# DDRMemory.net
KiCad netlist of a schematic drawn in Altium Designer
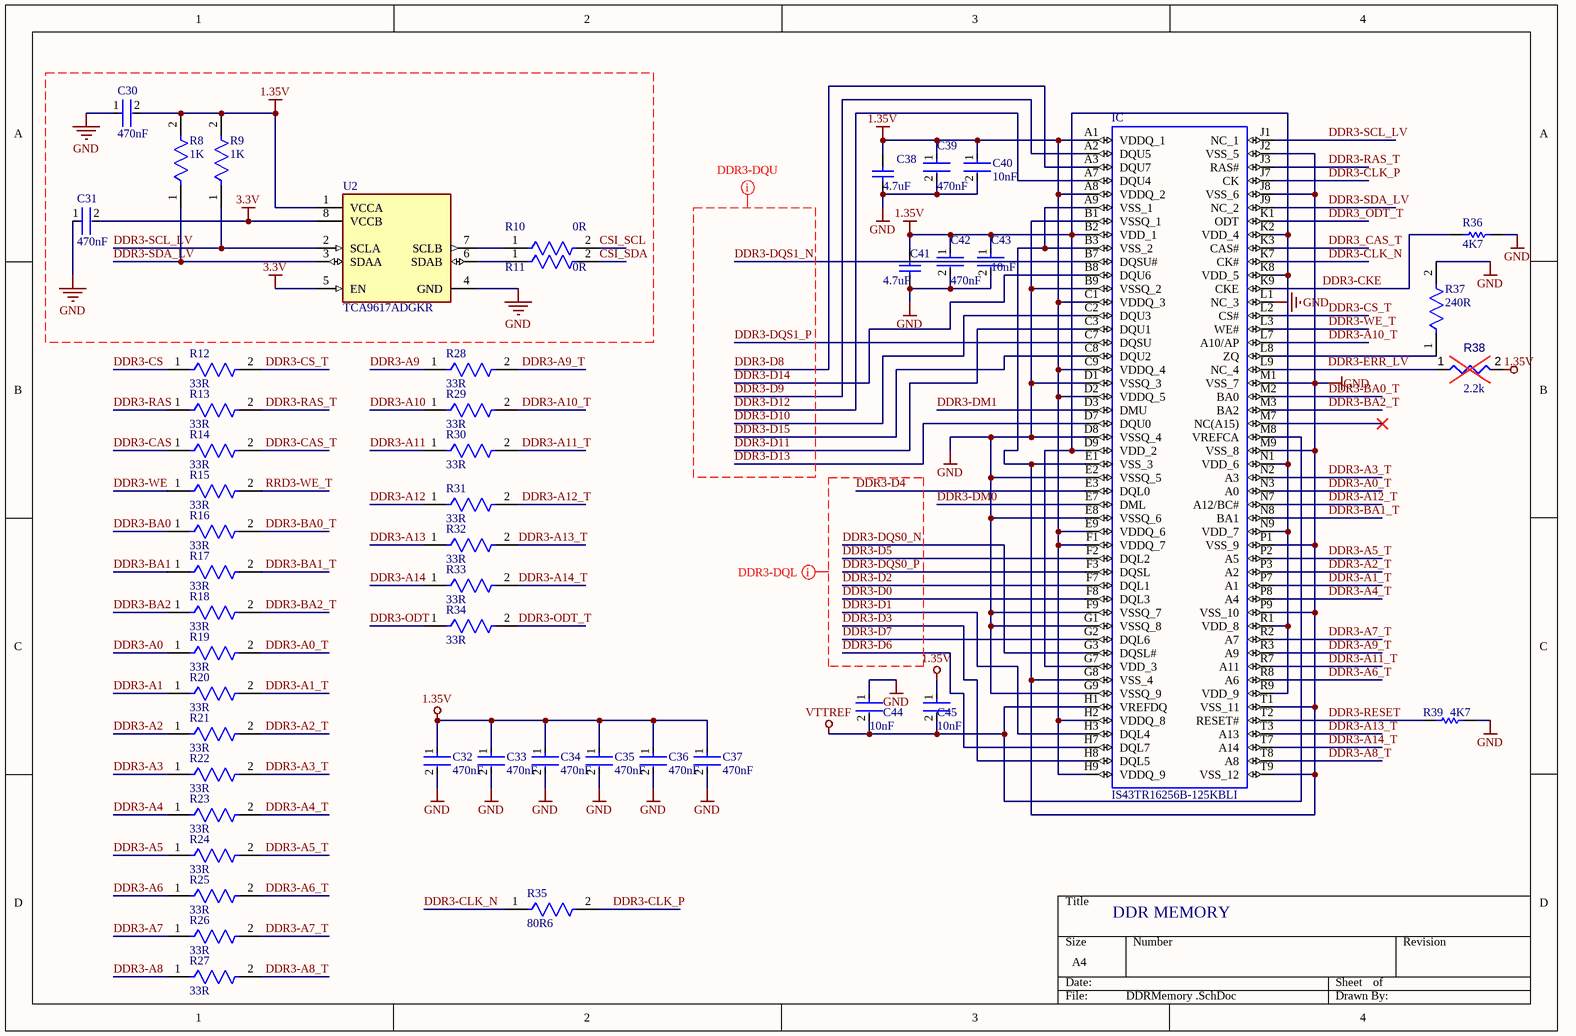
[diagram p0: DDRMemory .SchDoc]

(export (version "E")
  (design (tool "Eeschema 10.0.6"))
  (components
    (comp (ref "C30")
      (value "470nF")
      (footprint "FP-CC0603-DA-MFG")
      (description "CAP CER 0.47UF 6.3V X5R 0603")
      (fields
        (field (name "VOLTAGE") "6.3 V")
        (field (name "OCTOPART") "https://octopart.com/cc0603krx5r5bb474-yageo-9288194")
      )
      (libsource (lib "Altium Content Vault") (part "11868f565c42a9108669ba33697ecf6"))
    )
    (comp (ref "C31")
      (value "470nF")
      (footprint "FP-CC0603-DA-MFG")
      (description "CAP CER 0.47UF 6.3V X5R 0603")
      (fields
        (field (name "VOLTAGE") "6.3 V")
        (field (name "OCTOPART") "https://octopart.com/cc0603krx5r5bb474-yageo-9288194")
      )
      (libsource (lib "Altium Content Vault") (part "11868f565c42a9108669ba33697ecf6"))
    )
    (comp (ref "C32")
      (value "470nF")
      (footprint "FP-0603-L_1_6_0_1-W_0_8_0-IPC_C")
      (description "None")
      (fields (field (name "TOLERANCE") "20%"))
      (libsource (lib "Altium Content Vault") (part "02cd4be3c70576c341d710602a673aa"))
    )
    (comp (ref "C33")
      (value "470nF")
      (footprint "FP-0603-L_1_6_0_1-W_0_8_0-IPC_C")
      (description "None")
      (fields (field (name "TOLERANCE") "20%"))
      (libsource (lib "Altium Content Vault") (part "02cd4be3c70576c341d710602a673aa"))
    )
    (comp (ref "C34")
      (value "470nF")
      (footprint "FP-0603-L_1_6_0_1-W_0_8_0-IPC_C")
      (description "None")
      (fields (field (name "TOLERANCE") "20%"))
      (libsource (lib "Altium Content Vault") (part "02cd4be3c70576c341d710602a673aa"))
    )
    (comp (ref "C35")
      (value "470nF")
      (footprint "FP-0603-L_1_6_0_1-W_0_8_0-IPC_C")
      (description "None")
      (fields (field (name "TOLERANCE") "20%"))
      (libsource (lib "Altium Content Vault") (part "02cd4be3c70576c341d710602a673aa"))
    )
    (comp (ref "C36")
      (value "470nF")
      (footprint "FP-0603-L_1_6_0_1-W_0_8_0-IPC_C")
      (description "None")
      (fields (field (name "TOLERANCE") "20%"))
      (libsource (lib "Altium Content Vault") (part "02cd4be3c70576c341d710602a673aa"))
    )
    (comp (ref "C37")
      (value "470nF")
      (footprint "FP-0603-L_1_6_0_1-W_0_8_0-IPC_C")
      (description "None")
      (fields (field (name "TOLERANCE") "20%"))
      (libsource (lib "Altium Content Vault") (part "02cd4be3c70576c341d710602a673aa"))
    )
    (comp (ref "C38")
      (value "4.7uF")
      (footprint "CAPC1005X71X25NL10T15")
      (fields
        (field (name "PART NUMBER") "0402ZD475MAT2A")
        (field (name "MANUFACTURER") "AVX Interconnect / Elco")
      )
      (libsource (lib "Altium Content Vault") (part "CAP"))
    )
    (comp (ref "C39")
      (value "470nF")
      (footprint "FP-0402-L_1_0_1-W_0_5_0_1-IPC_C")
      (description "General Purpose Ceramic Capacitor, 0402, 470nF, 10%, X7R, 15%, 10V")
      (libsource (lib "Altium Content Vault") (part "b4654b650e69147ec39a6b967a45e02"))
    )
    (comp (ref "C40")
      (value "10nF")
      (footprint "FP-CC0402-MFG")
      (description "CAP CER 10000PF 10V X7R 0402")
      (fields
        (field (name "MANUFACTURER PART NUMBER") "CC0402MRX7R6BB103")
        (field (name "MANUFACTURER") "YAGEO")
      )
      (libsource (lib "Altium Content Vault") (part "11868f565c42a9108669ba33697ecf6"))
    )
    (comp (ref "C41")
      (value "4.7uF")
      (footprint "CAPC1005X71X25NL10T15")
      (fields
        (field (name "PART NUMBER") "0402ZD475MAT2A")
        (field (name "MANUFACTURER") "AVX Interconnect / Elco")
      )
      (libsource (lib "Altium Content Vault") (part "CAP"))
    )
    (comp (ref "C42")
      (value "470nF")
      (footprint "FP-0402-L_1_0_1-W_0_5_0_1-IPC_C")
      (description "General Purpose Ceramic Capacitor, 0402, 470nF, 10%, X7R, 15%, 10V")
      (libsource (lib "Altium Content Vault") (part "b4654b650e69147ec39a6b967a45e02"))
    )
    (comp (ref "C43")
      (value "10nF")
      (footprint "FP-CC0402-MFG")
      (description "CAP CER 10000PF 10V X7R 0402")
      (fields
        (field (name "MANUFACTURER PART NUMBER") "CC0402MRX7R6BB103")
        (field (name "MANUFACTURER") "YAGEO")
      )
      (libsource (lib "Altium Content Vault") (part "11868f565c42a9108669ba33697ecf6"))
    )
    (comp (ref "C44")
      (value "10nF")
      (footprint "FP-CC0402-MFG")
      (description "CAP CER 10000PF 10V X7R 0402")
      (fields
        (field (name "MANUFACTURER PART NUMBER") "CC0402MRX7R6BB103")
        (field (name "MANUFACTURER") "YAGEO")
      )
      (libsource (lib "Altium Content Vault") (part "11868f565c42a9108669ba33697ecf6"))
    )
    (comp (ref "C45")
      (value "10nF")
      (footprint "FP-CC0402-MFG")
      (description "CAP CER 10000PF 10V X7R 0402")
      (fields
        (field (name "MANUFACTURER PART NUMBER") "CC0402MRX7R6BB103")
        (field (name "MANUFACTURER") "YAGEO")
      )
      (libsource (lib "Altium Content Vault") (part "11868f565c42a9108669ba33697ecf6"))
    )
    (comp (ref "IC")
      (value "IS43TR16256B-125KBLI")
      (footprint "BGA96C80P9X16_900X1300X120:BGA96C80P9X16_900X1300X120")
      (description "SDRAM - DDR3 Memory IC 4Gb (256M x 16) Parallel 800MHz 20ns 96-TWBGA (9x13)")
      (fields (field (name "MF") "ISSI, Integrated Silicon Solution Inc"))
      (libsource (lib "IS43TR16256B-125KBLI") (part "IS43TR16256B-125KBLI"))
    )
    (comp (ref "R8")
      (value "1K")
      (footprint "FP-AC0603-IPC_B")
      (description "RES 1kΩ 1.00% 0.2W 0603")
      (libsource (lib "Altium Content Vault") (part "1029c3af85768c4190bb7ad29bc67b5"))
    )
    (comp (ref "R9")
      (value "1K")
      (footprint "FP-AC0603-IPC_B")
      (description "RES 1kΩ 1.00% 0.2W 0603")
      (libsource (lib "Altium Content Vault") (part "1029c3af85768c4190bb7ad29bc67b5"))
    )
    (comp (ref "R10")
      (value "0R")
      (footprint "FP-AC0603-IPC_A")
      (description "RES 0Ω 0.00% 0.1W 0603")
      (fields (field (name "TOLERANCE") "5%"))
      (libsource (lib "Altium Content Vault") (part "1029c3af85768c4190bb7ad29bc67b5"))
    )
    (comp (ref "R11")
      (value "0R")
      (footprint "FP-AC0603-IPC_A")
      (description "RES 0Ω 0.00% 0.1W 0603")
      (fields (field (name "TOLERANCE") "5%"))
      (libsource (lib "Altium Content Vault") (part "1029c3af85768c4190bb7ad29bc67b5"))
    )
    (comp (ref "R12")
      (value "33R")
      (footprint "FP-AF0201-IPC_A")
      (description "Anti-Sulfurated Chip Resistors Automotive Grade 33Ω 5% 200ppm/°C 0201")
      (fields (field (name "TOLERANCE") "5%"))
      (libsource (lib "Altium Content Vault") (part "1029c3af85768c4190bb7ad29bc67b5"))
    )
    (comp (ref "R13")
      (value "33R")
      (footprint "FP-AF0201-IPC_A")
      (description "Anti-Sulfurated Chip Resistors Automotive Grade 33Ω 5% 200ppm/°C 0201")
      (fields (field (name "TOLERANCE") "5%"))
      (libsource (lib "Altium Content Vault") (part "1029c3af85768c4190bb7ad29bc67b5"))
    )
    (comp (ref "R14")
      (value "33R")
      (footprint "FP-AF0201-IPC_A")
      (description "Anti-Sulfurated Chip Resistors Automotive Grade 33Ω 5% 200ppm/°C 0201")
      (fields (field (name "TOLERANCE") "5%"))
      (libsource (lib "Altium Content Vault") (part "1029c3af85768c4190bb7ad29bc67b5"))
    )
    (comp (ref "R15")
      (value "33R")
      (footprint "FP-AF0201-IPC_A")
      (description "Anti-Sulfurated Chip Resistors Automotive Grade 33Ω 5% 200ppm/°C 0201")
      (fields (field (name "TOLERANCE") "5%"))
      (libsource (lib "Altium Content Vault") (part "1029c3af85768c4190bb7ad29bc67b5"))
    )
    (comp (ref "R16")
      (value "33R")
      (footprint "FP-AF0201-IPC_A")
      (description "Anti-Sulfurated Chip Resistors Automotive Grade 33Ω 5% 200ppm/°C 0201")
      (fields (field (name "TOLERANCE") "5%"))
      (libsource (lib "Altium Content Vault") (part "1029c3af85768c4190bb7ad29bc67b5"))
    )
    (comp (ref "R17")
      (value "33R")
      (footprint "FP-AF0201-IPC_A")
      (description "Anti-Sulfurated Chip Resistors Automotive Grade 33Ω 5% 200ppm/°C 0201")
      (fields (field (name "TOLERANCE") "5%"))
      (libsource (lib "Altium Content Vault") (part "1029c3af85768c4190bb7ad29bc67b5"))
    )
    (comp (ref "R18")
      (value "33R")
      (footprint "FP-AF0201-IPC_A")
      (description "Anti-Sulfurated Chip Resistors Automotive Grade 33Ω 5% 200ppm/°C 0201")
      (fields (field (name "TOLERANCE") "5%"))
      (libsource (lib "Altium Content Vault") (part "1029c3af85768c4190bb7ad29bc67b5"))
    )
    (comp (ref "R19")
      (value "33R")
      (footprint "FP-AF0201-IPC_A")
      (description "Anti-Sulfurated Chip Resistors Automotive Grade 33Ω 5% 200ppm/°C 0201")
      (fields (field (name "TOLERANCE") "5%"))
      (libsource (lib "Altium Content Vault") (part "1029c3af85768c4190bb7ad29bc67b5"))
    )
    (comp (ref "R20")
      (value "33R")
      (footprint "FP-AF0201-IPC_A")
      (description "Anti-Sulfurated Chip Resistors Automotive Grade 33Ω 5% 200ppm/°C 0201")
      (fields (field (name "TOLERANCE") "5%"))
      (libsource (lib "Altium Content Vault") (part "1029c3af85768c4190bb7ad29bc67b5"))
    )
    (comp (ref "R21")
      (value "33R")
      (footprint "FP-AF0201-IPC_A")
      (description "Anti-Sulfurated Chip Resistors Automotive Grade 33Ω 5% 200ppm/°C 0201")
      (fields (field (name "TOLERANCE") "5%"))
      (libsource (lib "Altium Content Vault") (part "1029c3af85768c4190bb7ad29bc67b5"))
    )
    (comp (ref "R22")
      (value "33R")
      (footprint "FP-AF0201-IPC_A")
      (description "Anti-Sulfurated Chip Resistors Automotive Grade 33Ω 5% 200ppm/°C 0201")
      (fields (field (name "TOLERANCE") "5%"))
      (libsource (lib "Altium Content Vault") (part "1029c3af85768c4190bb7ad29bc67b5"))
    )
    (comp (ref "R23")
      (value "33R")
      (footprint "FP-AF0201-IPC_A")
      (description "Anti-Sulfurated Chip Resistors Automotive Grade 33Ω 5% 200ppm/°C 0201")
      (fields (field (name "TOLERANCE") "5%"))
      (libsource (lib "Altium Content Vault") (part "1029c3af85768c4190bb7ad29bc67b5"))
    )
    (comp (ref "R24")
      (value "33R")
      (footprint "FP-AF0201-IPC_A")
      (description "Anti-Sulfurated Chip Resistors Automotive Grade 33Ω 5% 200ppm/°C 0201")
      (fields (field (name "TOLERANCE") "5%"))
      (libsource (lib "Altium Content Vault") (part "1029c3af85768c4190bb7ad29bc67b5"))
    )
    (comp (ref "R25")
      (value "33R")
      (footprint "FP-AF0201-IPC_A")
      (description "Anti-Sulfurated Chip Resistors Automotive Grade 33Ω 5% 200ppm/°C 0201")
      (fields (field (name "TOLERANCE") "5%"))
      (libsource (lib "Altium Content Vault") (part "1029c3af85768c4190bb7ad29bc67b5"))
    )
    (comp (ref "R26")
      (value "33R")
      (footprint "FP-AF0201-IPC_A")
      (description "Anti-Sulfurated Chip Resistors Automotive Grade 33Ω 5% 200ppm/°C 0201")
      (fields (field (name "TOLERANCE") "5%"))
      (libsource (lib "Altium Content Vault") (part "1029c3af85768c4190bb7ad29bc67b5"))
    )
    (comp (ref "R27")
      (value "33R")
      (footprint "FP-AF0201-IPC_A")
      (description "Anti-Sulfurated Chip Resistors Automotive Grade 33Ω 5% 200ppm/°C 0201")
      (fields (field (name "TOLERANCE") "5%"))
      (libsource (lib "Altium Content Vault") (part "1029c3af85768c4190bb7ad29bc67b5"))
    )
    (comp (ref "R28")
      (value "33R")
      (footprint "FP-AF0201-IPC_A")
      (description "Anti-Sulfurated Chip Resistors Automotive Grade 33Ω 5% 200ppm/°C 0201")
      (fields (field (name "TOLERANCE") "5%"))
      (libsource (lib "Altium Content Vault") (part "1029c3af85768c4190bb7ad29bc67b5"))
    )
    (comp (ref "R29")
      (value "33R")
      (footprint "FP-AF0201-IPC_A")
      (description "Anti-Sulfurated Chip Resistors Automotive Grade 33Ω 5% 200ppm/°C 0201")
      (fields (field (name "TOLERANCE") "5%"))
      (libsource (lib "Altium Content Vault") (part "1029c3af85768c4190bb7ad29bc67b5"))
    )
    (comp (ref "R30")
      (value "33R")
      (footprint "FP-AF0201-IPC_A")
      (description "Anti-Sulfurated Chip Resistors Automotive Grade 33Ω 5% 200ppm/°C 0201")
      (fields (field (name "TOLERANCE") "5%"))
      (libsource (lib "Altium Content Vault") (part "1029c3af85768c4190bb7ad29bc67b5"))
    )
    (comp (ref "R31")
      (value "33R")
      (footprint "FP-AF0201-IPC_A")
      (description "Anti-Sulfurated Chip Resistors Automotive Grade 33Ω 5% 200ppm/°C 0201")
      (fields (field (name "TOLERANCE") "5%"))
      (libsource (lib "Altium Content Vault") (part "1029c3af85768c4190bb7ad29bc67b5"))
    )
    (comp (ref "R32")
      (value "33R")
      (footprint "FP-AF0201-IPC_A")
      (description "Anti-Sulfurated Chip Resistors Automotive Grade 33Ω 5% 200ppm/°C 0201")
      (fields (field (name "TOLERANCE") "5%"))
      (libsource (lib "Altium Content Vault") (part "1029c3af85768c4190bb7ad29bc67b5"))
    )
    (comp (ref "R33")
      (value "33R")
      (footprint "FP-AF0201-IPC_A")
      (description "Anti-Sulfurated Chip Resistors Automotive Grade 33Ω 5% 200ppm/°C 0201")
      (fields (field (name "TOLERANCE") "5%"))
      (libsource (lib "Altium Content Vault") (part "1029c3af85768c4190bb7ad29bc67b5"))
    )
    (comp (ref "R34")
      (value "33R")
      (footprint "FP-AF0201-IPC_A")
      (description "Anti-Sulfurated Chip Resistors Automotive Grade 33Ω 5% 200ppm/°C 0201")
      (fields (field (name "TOLERANCE") "5%"))
      (libsource (lib "Altium Content Vault") (part "1029c3af85768c4190bb7ad29bc67b5"))
    )
    (comp (ref "R35")
      (value "80R6")
      (footprint "FP-RQ732B-IPC_C")
      (description "RQ732B 1206 80.6Ω 0.4W 10ppm/°C 0.1% 200V")
      (fields (field (name "TOLERANCE") "0.1%") (field (name "MANUFACTURER PART NUMBER") "RQ73C2B80R6BTDF"))
      (libsource (lib "Altium Content Vault") (part "1029c3af85768c4190bb7ad29bc67b5"))
    )
    (comp (ref "R36")
      (value "4K7")
      (footprint "RESC1812(4532)_N")
      (description "4K7 0.75W 5% 1812 (4532 Metric)  SMD")
      (fields (field (name "TOLERANCE") "5 %") (field (name "POWER") "0.75 W"))
      (libsource (lib "Altium Content Vault") (part "RES"))
    )
    (comp (ref "R37")
      (value "240R")
      (footprint "FP-RNCP0402-IPC_C")
      (description "240Ω ±1% 0.1W 0402 High Power Anti-Sulfur Thin Film Chip Resistor")
      (fields (field (name "TOLERANCE") "1%"))
      (libsource (lib "Altium Content Vault") (part "1029c3af85768c4190bb7ad29bc67b5"))
    )
    (comp (ref "R38")
      (value "2.2k")
      (footprint "RESC0402(1005)_L")
      (description "2K2 0.063W 5% 0402 (1005 Metric)  SMD")
      (fields (field (name "TOLERANCE") "5%") (field (name "POWER") "63mW"))
      (libsource (lib "Meenakshi Shyam") (part "2D2KR2J"))
    )
    (comp (ref "R39")
      (value "4K7")
      (footprint "RESC1812(4532)_N")
      (description "4K7 0.75W 5% 1812 (4532 Metric)  SMD")
      (fields (field (name "TOLERANCE") "5 %") (field (name "POWER") "0.75 W"))
      (libsource (lib "Altium Content Vault") (part "RES"))
    )
    (comp (ref "U2")
      (value "TCA9617ADGKR")
      (footprint "FP-DGK0008A-MFG")
      (description "IC TRNSLTR BIDIRECTIONAL 8VSSOP")
      (fields
        (field (name "MANUFACTURER") "Texas Instruments")
        (field (name "OCTOPART") "https://octopart.com/tca9617adgkr-texas+instruments-29775809")
      )
      (libsource (lib "Altium Content Vault") (part "d64de71481be55f428f1ea82f36f333"))
    )
  )
  (nets
    (net (code "1") (name "/CSI_SCL") (class "Default")
      (node (ref "R10") (pin "2") (pinfunction "2_2") (pintype "passive"))
    )
    (net (code "2") (name "/CSI_SDA") (class "Default")
      (node (ref "R11") (pin "2") (pinfunction "2_2") (pintype "passive"))
    )
    (net (code "3") (name "/DDR3-A0") (class "Default")
      (node (ref "R19") (pin "1") (pinfunction "1_1") (pintype "passive"))
    )
    (net (code "4") (name "/DDR3-A0_T") (class "Default")
      (node (ref "IC") (pin "N3") (pinfunction "A0_N3") (pintype "bidirectional"))
      (node (ref "R19") (pin "2") (pinfunction "2_2") (pintype "passive"))
    )
    (net (code "5") (name "/DDR3-A1") (class "Default")
      (node (ref "R20") (pin "1") (pinfunction "1_1") (pintype "passive"))
    )
    (net (code "6") (name "/DDR3-A1_T") (class "Default")
      (node (ref "IC") (pin "P7") (pinfunction "A1_P7") (pintype "bidirectional"))
      (node (ref "R20") (pin "2") (pinfunction "2_2") (pintype "passive"))
    )
    (net (code "7") (name "/DDR3-A2") (class "Default")
      (node (ref "R21") (pin "1") (pinfunction "1_1") (pintype "passive"))
    )
    (net (code "8") (name "/DDR3-A2_T") (class "Default")
      (node (ref "IC") (pin "P3") (pinfunction "A2_P3") (pintype "bidirectional"))
      (node (ref "R21") (pin "2") (pinfunction "2_2") (pintype "passive"))
    )
    (net (code "9") (name "/DDR3-A3") (class "Default")
      (node (ref "R22") (pin "1") (pinfunction "1_1") (pintype "passive"))
    )
    (net (code "10") (name "/DDR3-A3_T") (class "Default")
      (node (ref "IC") (pin "N2") (pinfunction "A3_N2") (pintype "bidirectional"))
      (node (ref "R22") (pin "2") (pinfunction "2_2") (pintype "passive"))
    )
    (net (code "11") (name "/DDR3-A4") (class "Default")
      (node (ref "R23") (pin "1") (pinfunction "1_1") (pintype "passive"))
    )
    (net (code "12") (name "/DDR3-A4_T") (class "Default")
      (node (ref "IC") (pin "P8") (pinfunction "A4_P8") (pintype "bidirectional"))
      (node (ref "R23") (pin "2") (pinfunction "2_2") (pintype "passive"))
    )
    (net (code "13") (name "/DDR3-A5") (class "Default")
      (node (ref "R24") (pin "1") (pinfunction "1_1") (pintype "passive"))
    )
    (net (code "14") (name "/DDR3-A5_T") (class "Default")
      (node (ref "IC") (pin "P2") (pinfunction "A5_P2") (pintype "bidirectional"))
      (node (ref "R24") (pin "2") (pinfunction "2_2") (pintype "passive"))
    )
    (net (code "15") (name "/DDR3-A6") (class "Default")
      (node (ref "R25") (pin "1") (pinfunction "1_1") (pintype "passive"))
    )
    (net (code "16") (name "/DDR3-A6_T") (class "Default")
      (node (ref "IC") (pin "R8") (pinfunction "A6_R8") (pintype "bidirectional"))
      (node (ref "R25") (pin "2") (pinfunction "2_2") (pintype "passive"))
    )
    (net (code "17") (name "/DDR3-A7") (class "Default")
      (node (ref "R26") (pin "1") (pinfunction "1_1") (pintype "passive"))
    )
    (net (code "18") (name "/DDR3-A7_T") (class "Default")
      (node (ref "IC") (pin "R2") (pinfunction "A7_R2") (pintype "bidirectional"))
      (node (ref "R26") (pin "2") (pinfunction "2_2") (pintype "passive"))
    )
    (net (code "19") (name "/DDR3-A8") (class "Default")
      (node (ref "R27") (pin "1") (pinfunction "1_1") (pintype "passive"))
    )
    (net (code "20") (name "/DDR3-A8_T") (class "Default")
      (node (ref "IC") (pin "T8") (pinfunction "A8_T8") (pintype "bidirectional"))
      (node (ref "R27") (pin "2") (pinfunction "2_2") (pintype "passive"))
    )
    (net (code "21") (name "/DDR3-A9") (class "Default")
      (node (ref "R28") (pin "1") (pinfunction "1_1") (pintype "passive"))
    )
    (net (code "22") (name "/DDR3-A9_T") (class "Default")
      (node (ref "IC") (pin "R3") (pinfunction "A9_R3") (pintype "bidirectional"))
      (node (ref "R28") (pin "2") (pinfunction "2_2") (pintype "passive"))
    )
    (net (code "23") (name "/DDR3-A10") (class "Default")
      (node (ref "R29") (pin "1") (pinfunction "1_1") (pintype "passive"))
    )
    (net (code "24") (name "/DDR3-A10_T") (class "Default")
      (node (ref "IC") (pin "L7") (pinfunction "A10/AP_L7") (pintype "bidirectional"))
      (node (ref "R29") (pin "2") (pinfunction "2_2") (pintype "passive"))
    )
    (net (code "25") (name "/DDR3-A11") (class "Default")
      (node (ref "R30") (pin "1") (pinfunction "1_1") (pintype "passive"))
    )
    (net (code "26") (name "/DDR3-A11_T") (class "Default")
      (node (ref "IC") (pin "R7") (pinfunction "A11_R7") (pintype "bidirectional"))
      (node (ref "R30") (pin "2") (pinfunction "2_2") (pintype "passive"))
    )
    (net (code "27") (name "/DDR3-A12") (class "Default")
      (node (ref "R31") (pin "1") (pinfunction "1_1") (pintype "passive"))
    )
    (net (code "28") (name "/DDR3-A12_T") (class "Default")
      (node (ref "IC") (pin "N7") (pinfunction "A12/BC#_N7") (pintype "bidirectional"))
      (node (ref "R31") (pin "2") (pinfunction "2_2") (pintype "passive"))
    )
    (net (code "29") (name "/DDR3-A13") (class "Default")
      (node (ref "R32") (pin "1") (pinfunction "1_1") (pintype "passive"))
    )
    (net (code "30") (name "/DDR3-A13_T") (class "Default")
      (node (ref "IC") (pin "T3") (pinfunction "A13_T3") (pintype "bidirectional"))
      (node (ref "R32") (pin "2") (pinfunction "2_2") (pintype "passive"))
    )
    (net (code "31") (name "/DDR3-A14") (class "Default")
      (node (ref "R33") (pin "1") (pinfunction "1_1") (pintype "passive"))
    )
    (net (code "32") (name "/DDR3-A14_T") (class "Default")
      (node (ref "IC") (pin "T7") (pinfunction "A14_T7") (pintype "bidirectional"))
      (node (ref "R33") (pin "2") (pinfunction "2_2") (pintype "passive"))
    )
    (net (code "33") (name "/DDR3-BA0") (class "Default")
      (node (ref "R16") (pin "1") (pinfunction "1_1") (pintype "passive"))
    )
    (net (code "34") (name "/DDR3-BA0_T") (class "Default")
      (node (ref "IC") (pin "M2") (pinfunction "BA0_M2") (pintype "bidirectional"))
      (node (ref "R16") (pin "2") (pinfunction "2_2") (pintype "passive"))
    )
    (net (code "35") (name "/DDR3-BA1") (class "Default")
      (node (ref "R17") (pin "1") (pinfunction "1_1") (pintype "passive"))
    )
    (net (code "36") (name "/DDR3-BA1_T") (class "Default")
      (node (ref "IC") (pin "N8") (pinfunction "BA1_N8") (pintype "bidirectional"))
      (node (ref "R17") (pin "2") (pinfunction "2_2") (pintype "passive"))
    )
    (net (code "37") (name "/DDR3-BA2") (class "Default")
      (node (ref "R18") (pin "1") (pinfunction "1_1") (pintype "passive"))
    )
    (net (code "38") (name "/DDR3-BA2_T") (class "Default")
      (node (ref "IC") (pin "M3") (pinfunction "BA2_M3") (pintype "bidirectional"))
      (node (ref "R18") (pin "2") (pinfunction "2_2") (pintype "passive"))
    )
    (net (code "39") (name "/DDR3-CAS") (class "Default")
      (node (ref "R14") (pin "1") (pinfunction "1_1") (pintype "passive"))
    )
    (net (code "40") (name "/DDR3-CAS_T") (class "Default")
      (node (ref "R14") (pin "2") (pinfunction "2_2") (pintype "passive"))
    )
    (net (code "41") (name "/DDR3-CKE") (class "Default")
      (node (ref "IC") (pin "K9") (pinfunction "CKE_K9") (pintype "bidirectional"))
      (node (ref "R36") (pin "1") (pinfunction "1_1") (pintype "passive"))
    )
    (net (code "42") (name "/DDR3-CLK_N") (class "Default")
      (node (ref "IC") (pin "K7") (pinfunction "CK#_K7") (pintype "bidirectional"))
      (node (ref "R35") (pin "1") (pinfunction "1_1") (pintype "passive"))
    )
    (net (code "43") (name "/DDR3-CLK_P") (class "Default")
      (node (ref "IC") (pin "J7") (pinfunction "CK_J7") (pintype "bidirectional"))
      (node (ref "R35") (pin "2") (pinfunction "2_2") (pintype "passive"))
    )
    (net (code "44") (name "/DDR3-CS") (class "Default")
      (node (ref "R12") (pin "1") (pinfunction "1_1") (pintype "passive"))
    )
    (net (code "45") (name "/DDR3-CS_T") (class "Default")
      (node (ref "IC") (pin "L2") (pinfunction "CS#_L2") (pintype "bidirectional"))
      (node (ref "R12") (pin "2") (pinfunction "2_2") (pintype "passive"))
    )
    (net (code "46") (name "/DDR3-D0") (class "Default")
      (node (ref "IC") (pin "F8") (pinfunction "DQL3_F8") (pintype "bidirectional"))
    )
    (net (code "47") (name "/DDR3-D1") (class "Default")
      (node (ref "IC") (pin "H3") (pinfunction "DQL4_H3") (pintype "bidirectional"))
    )
    (net (code "48") (name "/DDR3-D2") (class "Default")
      (node (ref "IC") (pin "F7") (pinfunction "DQL1_F7") (pintype "bidirectional"))
    )
    (net (code "49") (name "/DDR3-D3") (class "Default")
      (node (ref "IC") (pin "H8") (pinfunction "DQL5_H8") (pintype "bidirectional"))
    )
    (net (code "50") (name "/DDR3-D4") (class "Default")
      (node (ref "IC") (pin "E3") (pinfunction "DQL0_E3") (pintype "bidirectional"))
    )
    (net (code "51") (name "/DDR3-D5") (class "Default")
      (node (ref "IC") (pin "F2") (pinfunction "DQL2_F2") (pintype "bidirectional"))
    )
    (net (code "52") (name "/DDR3-D6") (class "Default")
      (node (ref "IC") (pin "H7") (pinfunction "DQL7_H7") (pintype "bidirectional"))
    )
    (net (code "53") (name "/DDR3-D7") (class "Default")
      (node (ref "IC") (pin "G2") (pinfunction "DQL6_G2") (pintype "bidirectional"))
    )
    (net (code "54") (name "/DDR3-D8") (class "Default")
      (node (ref "IC") (pin "A3") (pinfunction "DQU7_A3") (pintype "bidirectional"))
    )
    (net (code "55") (name "/DDR3-D9") (class "Default")
      (node (ref "IC") (pin "A2") (pinfunction "DQU5_A2") (pintype "bidirectional"))
    )
    (net (code "56") (name "/DDR3-D10") (class "Default")
      (node (ref "IC") (pin "C2") (pinfunction "DQU3_C2") (pintype "bidirectional"))
    )
    (net (code "57") (name "/DDR3-D11") (class "Default")
      (node (ref "IC") (pin "C3") (pinfunction "DQU1_C3") (pintype "bidirectional"))
    )
    (net (code "58") (name "/DDR3-D12") (class "Default")
      (node (ref "IC") (pin "A7") (pinfunction "DQU4_A7") (pintype "bidirectional"))
    )
    (net (code "59") (name "/DDR3-D13") (class "Default")
      (node (ref "IC") (pin "D7") (pinfunction "DQU0_D7") (pintype "bidirectional"))
    )
    (net (code "60") (name "/DDR3-D14") (class "Default")
      (node (ref "IC") (pin "B8") (pinfunction "DQU6_B8") (pintype "bidirectional"))
    )
    (net (code "61") (name "/DDR3-D15") (class "Default")
      (node (ref "IC") (pin "C8") (pinfunction "DQU2_C8") (pintype "bidirectional"))
    )
    (net (code "62") (name "/DDR3-DM0") (class "Default")
      (node (ref "IC") (pin "E7") (pinfunction "DML_E7") (pintype "bidirectional"))
    )
    (net (code "63") (name "/DDR3-DM1") (class "Default")
      (node (ref "IC") (pin "D3") (pinfunction "DMU_D3") (pintype "bidirectional"))
    )
    (net (code "64") (name "/DDR3-DQS0_N") (class "Default")
      (node (ref "IC") (pin "G3") (pinfunction "DQSL#_G3") (pintype "bidirectional"))
    )
    (net (code "65") (name "/DDR3-DQS0_P") (class "Default")
      (node (ref "IC") (pin "F3") (pinfunction "DQSL_F3") (pintype "bidirectional"))
    )
    (net (code "66") (name "/DDR3-DQS1_N") (class "Default")
      (node (ref "IC") (pin "B7") (pinfunction "DQSU#_B7") (pintype "bidirectional"))
    )
    (net (code "67") (name "/DDR3-DQS1_P") (class "Default")
      (node (ref "IC") (pin "C7") (pinfunction "DQSU_C7") (pintype "bidirectional"))
    )
    (net (code "68") (name "/DDR3-ERR_LV") (class "Default")
      (node (ref "IC") (pin "L9") (pinfunction "NC_4_L9") (pintype "bidirectional"))
      (node (ref "R38") (pin "1") (pinfunction "1_1") (pintype "passive"))
    )
    (net (code "69") (name "/DDR3-ODT") (class "Default")
      (node (ref "R34") (pin "1") (pinfunction "1_1") (pintype "passive"))
    )
    (net (code "70") (name "/DDR3-ODT_T") (class "Default")
      (node (ref "R34") (pin "2") (pinfunction "2_2") (pintype "passive"))
    )
    (net (code "71") (name "/DDR3-RAS") (class "Default")
      (node (ref "R13") (pin "1") (pinfunction "1_1") (pintype "passive"))
    )
    (net (code "72") (name "/DDR3-RAS_T") (class "Default")
      (node (ref "IC") (pin "J3") (pinfunction "RAS#_J3") (pintype "bidirectional"))
      (node (ref "R13") (pin "2") (pinfunction "2_2") (pintype "passive"))
    )
    (net (code "73") (name "/DDR3-RESET") (class "Default")
      (node (ref "IC") (pin "T2") (pinfunction "RESET#_T2") (pintype "bidirectional"))
      (node (ref "R39") (pin "1") (pinfunction "1_1") (pintype "passive"))
    )
    (net (code "74") (name "/DDR3-SCL_LV") (class "Default")
      (node (ref "IC") (pin "J1") (pinfunction "NC_1_J1") (pintype "bidirectional"))
      (node (ref "R9") (pin "1") (pinfunction "1_1") (pintype "passive"))
      (node (ref "U2") (pin "2") (pinfunction "SCLA_2") (pintype "input"))
    )
    (net (code "75") (name "/DDR3-SDA_LV") (class "Default")
      (node (ref "IC") (pin "J9") (pinfunction "NC_2_J9") (pintype "bidirectional"))
      (node (ref "R8") (pin "1") (pinfunction "1_1") (pintype "passive"))
      (node (ref "U2") (pin "3") (pinfunction "SDAA_3") (pintype "bidirectional"))
    )
    (net (code "76") (name "/DDR3-WE") (class "Default")
      (node (ref "R15") (pin "1") (pinfunction "1_1") (pintype "passive"))
    )
    (net (code "77") (name "/DDR3-WE_T") (class "Default")
      (node (ref "IC") (pin "L3") (pinfunction "WE#_L3") (pintype "bidirectional"))
    )
    (net (code "78") (name "/DDR3_CAS_T") (class "Default")
      (node (ref "IC") (pin "K3") (pinfunction "CAS#_K3") (pintype "bidirectional"))
    )
    (net (code "79") (name "/DDR3_ODT_T") (class "Default")
      (node (ref "IC") (pin "K1") (pinfunction "ODT_K1") (pintype "bidirectional"))
    )
    (net (code "80") (name "/RRD3-WE_T") (class "Default")
      (node (ref "R15") (pin "2") (pinfunction "2_2") (pintype "passive"))
    )
    (net (code "81") (name "1.35V") (class "Default")
      (node (ref "C30") (pin "1") (pinfunction "1_1") (pintype "passive"))
      (node (ref "C30") (pin "2") (pinfunction "2_2") (pintype "passive"))
      (node (ref "C31") (pin "1") (pinfunction "1_1") (pintype "passive"))
      (node (ref "C32") (pin "1") (pinfunction "1_1") (pintype "passive"))
      (node (ref "C32") (pin "2") (pinfunction "2_2") (pintype "passive"))
      (node (ref "C33") (pin "1") (pinfunction "1_1") (pintype "passive"))
      (node (ref "C33") (pin "2") (pinfunction "2_2") (pintype "passive"))
      (node (ref "C34") (pin "1") (pinfunction "1_1") (pintype "passive"))
      (node (ref "C34") (pin "2") (pinfunction "2_2") (pintype "passive"))
      (node (ref "C35") (pin "1") (pinfunction "1_1") (pintype "passive"))
      (node (ref "C35") (pin "2") (pinfunction "2_2") (pintype "passive"))
      (node (ref "C36") (pin "1") (pinfunction "1_1") (pintype "passive"))
      (node (ref "C36") (pin "2") (pinfunction "2_2") (pintype "passive"))
      (node (ref "C37") (pin "1") (pinfunction "1_1") (pintype "passive"))
      (node (ref "C37") (pin "2") (pinfunction "2_2") (pintype "passive"))
      (node (ref "C38") (pin "1") (pinfunction "1_1") (pintype "passive"))
      (node (ref "C38") (pin "2") (pinfunction "2_2") (pintype "passive"))
      (node (ref "C39") (pin "1") (pinfunction "1_1") (pintype "passive"))
      (node (ref "C39") (pin "2") (pinfunction "2_2") (pintype "passive"))
      (node (ref "C40") (pin "1") (pinfunction "1_1") (pintype "passive"))
      (node (ref "C40") (pin "2") (pinfunction "2_2") (pintype "passive"))
      (node (ref "C41") (pin "1") (pinfunction "1_1") (pintype "passive"))
      (node (ref "C41") (pin "2") (pinfunction "2_2") (pintype "passive"))
      (node (ref "C42") (pin "1") (pinfunction "1_1") (pintype "passive"))
      (node (ref "C42") (pin "2") (pinfunction "2_2") (pintype "passive"))
      (node (ref "C43") (pin "1") (pinfunction "1_1") (pintype "passive"))
      (node (ref "C43") (pin "2") (pinfunction "2_2") (pintype "passive"))
      (node (ref "C44") (pin "1") (pinfunction "1_1") (pintype "passive"))
      (node (ref "C45") (pin "1") (pinfunction "1_1") (pintype "passive"))
      (node (ref "IC") (pin "A1") (pinfunction "VDDQ_1_A1") (pintype "bidirectional"))
      (node (ref "IC") (pin "A8") (pinfunction "VDDQ_2_A8") (pintype "bidirectional"))
      (node (ref "IC") (pin "A9") (pinfunction "VSS_1_A9") (pintype "bidirectional"))
      (node (ref "IC") (pin "B1") (pinfunction "VSSQ_1_B1") (pintype "bidirectional"))
      (node (ref "IC") (pin "B2") (pinfunction "VDD_1_B2") (pintype "bidirectional"))
      (node (ref "IC") (pin "B3") (pinfunction "VSS_2_B3") (pintype "bidirectional"))
      (node (ref "IC") (pin "B9") (pinfunction "VSSQ_2_B9") (pintype "bidirectional"))
      (node (ref "IC") (pin "C1") (pinfunction "VDDQ_3_C1") (pintype "bidirectional"))
      (node (ref "IC") (pin "C9") (pinfunction "VDDQ_4_C9") (pintype "bidirectional"))
      (node (ref "IC") (pin "D1") (pinfunction "VSSQ_3_D1") (pintype "bidirectional"))
      (node (ref "IC") (pin "D2") (pinfunction "VDDQ_5_D2") (pintype "bidirectional"))
      (node (ref "IC") (pin "D8") (pinfunction "VSSQ_4_D8") (pintype "bidirectional"))
      (node (ref "IC") (pin "D9") (pinfunction "VDD_2_D9") (pintype "bidirectional"))
      (node (ref "IC") (pin "E1") (pinfunction "VSS_3_E1") (pintype "bidirectional"))
      (node (ref "IC") (pin "E2") (pinfunction "VSSQ_5_E2") (pintype "bidirectional"))
      (node (ref "IC") (pin "E8") (pinfunction "VSSQ_6_E8") (pintype "bidirectional"))
      (node (ref "IC") (pin "E9") (pinfunction "VDDQ_6_E9") (pintype "bidirectional"))
      (node (ref "IC") (pin "F1") (pinfunction "VDDQ_7_F1") (pintype "bidirectional"))
      (node (ref "IC") (pin "F9") (pinfunction "VSSQ_7_F9") (pintype "bidirectional"))
      (node (ref "IC") (pin "G1") (pinfunction "VSSQ_8_G1") (pintype "bidirectional"))
      (node (ref "IC") (pin "G7") (pinfunction "VDD_3_G7") (pintype "bidirectional"))
      (node (ref "IC") (pin "G8") (pinfunction "VSS_4_G8") (pintype "bidirectional"))
      (node (ref "IC") (pin "G9") (pinfunction "VSSQ_9_G9") (pintype "bidirectional"))
      (node (ref "IC") (pin "H2") (pinfunction "VDDQ_8_H2") (pintype "bidirectional"))
      (node (ref "IC") (pin "H9") (pinfunction "VDDQ_9_H9") (pintype "bidirectional"))
      (node (ref "IC") (pin "J2") (pinfunction "VSS_5_J2") (pintype "bidirectional"))
      (node (ref "IC") (pin "J8") (pinfunction "VSS_6_J8") (pintype "bidirectional"))
      (node (ref "IC") (pin "K2") (pinfunction "VDD_4_K2") (pintype "bidirectional"))
      (node (ref "IC") (pin "K8") (pinfunction "VDD_5_K8") (pintype "bidirectional"))
      (node (ref "IC") (pin "L1") (pinfunction "NC_3_L1") (pintype "bidirectional"))
      (node (ref "IC") (pin "M1") (pinfunction "VSS_7_M1") (pintype "bidirectional"))
      (node (ref "IC") (pin "M9") (pinfunction "VSS_8_M9") (pintype "bidirectional"))
      (node (ref "IC") (pin "N1") (pinfunction "VDD_6_N1") (pintype "bidirectional"))
      (node (ref "IC") (pin "N9") (pinfunction "VDD_7_N9") (pintype "bidirectional"))
      (node (ref "IC") (pin "P1") (pinfunction "VSS_9_P1") (pintype "bidirectional"))
      (node (ref "IC") (pin "P9") (pinfunction "VSS_10_P9") (pintype "bidirectional"))
      (node (ref "IC") (pin "R1") (pinfunction "VDD_8_R1") (pintype "bidirectional"))
      (node (ref "IC") (pin "R9") (pinfunction "VDD_9_R9") (pintype "bidirectional"))
      (node (ref "IC") (pin "T1") (pinfunction "VSS_11_T1") (pintype "bidirectional"))
      (node (ref "IC") (pin "T9") (pinfunction "VSS_12_T9") (pintype "bidirectional"))
      (node (ref "R36") (pin "2") (pinfunction "2_2") (pintype "passive"))
      (node (ref "R37") (pin "2") (pinfunction "2_2") (pintype "passive"))
      (node (ref "R38") (pin "2") (pinfunction "2_2") (pintype "passive"))
      (node (ref "R39") (pin "2") (pinfunction "2_2") (pintype "passive"))
      (node (ref "R8") (pin "2") (pinfunction "2_2") (pintype "passive"))
      (node (ref "R9") (pin "2") (pinfunction "2_2") (pintype "passive"))
      (node (ref "U2") (pin "1") (pinfunction "VCCA_1") (pintype "power_in"))
      (node (ref "U2") (pin "4") (pinfunction "GND_4") (pintype "power_in"))
    )
    (net (code "82") (name "3.3V") (class "Default")
      (node (ref "C31") (pin "2") (pinfunction "2_2") (pintype "passive"))
      (node (ref "U2") (pin "5") (pinfunction "EN_5") (pintype "input"))
      (node (ref "U2") (pin "8") (pinfunction "VCCB_8") (pintype "power_in"))
    )
    (net (code "83") (name "Net-(IC-ZQ)") (class "Default")
      (node (ref "IC") (pin "L8") (pinfunction "ZQ_L8") (pintype "bidirectional"))
      (node (ref "R37") (pin "1") (pinfunction "1_1") (pintype "passive"))
    )
    (net (code "84") (name "Net-(U2-SCLB)") (class "Default")
      (node (ref "R10") (pin "1") (pinfunction "1_1") (pintype "passive"))
      (node (ref "U2") (pin "7") (pinfunction "SCLB_7") (pintype "output"))
    )
    (net (code "85") (name "Net-(U2-SDAB)") (class "Default")
      (node (ref "R11") (pin "1") (pinfunction "1_1") (pintype "passive"))
      (node (ref "U2") (pin "6") (pinfunction "SDAB_6") (pintype "bidirectional"))
    )
    (net (code "86") (name "VTTREF") (class "Default")
      (node (ref "C44") (pin "2") (pinfunction "2_2") (pintype "passive"))
      (node (ref "C45") (pin "2") (pinfunction "2_2") (pintype "passive"))
      (node (ref "IC") (pin "H1") (pinfunction "VREFDQ_H1") (pintype "bidirectional"))
      (node (ref "IC") (pin "M8") (pinfunction "VREFCA_M8") (pintype "bidirectional"))
    )
    (net (code "87") (name "unconnected-(IC-NC(A15)-PadM7)") (class "Default")
      (node (ref "IC") (pin "M7") (pinfunction "NC(A15)_M7") (pintype "bidirectional+no_connect"))
    )
  )
)
